# SCH_Andrew_s-NFC-Card_2024-04-20.net
KiCad netlist of a schematic drawn in EasyEDA
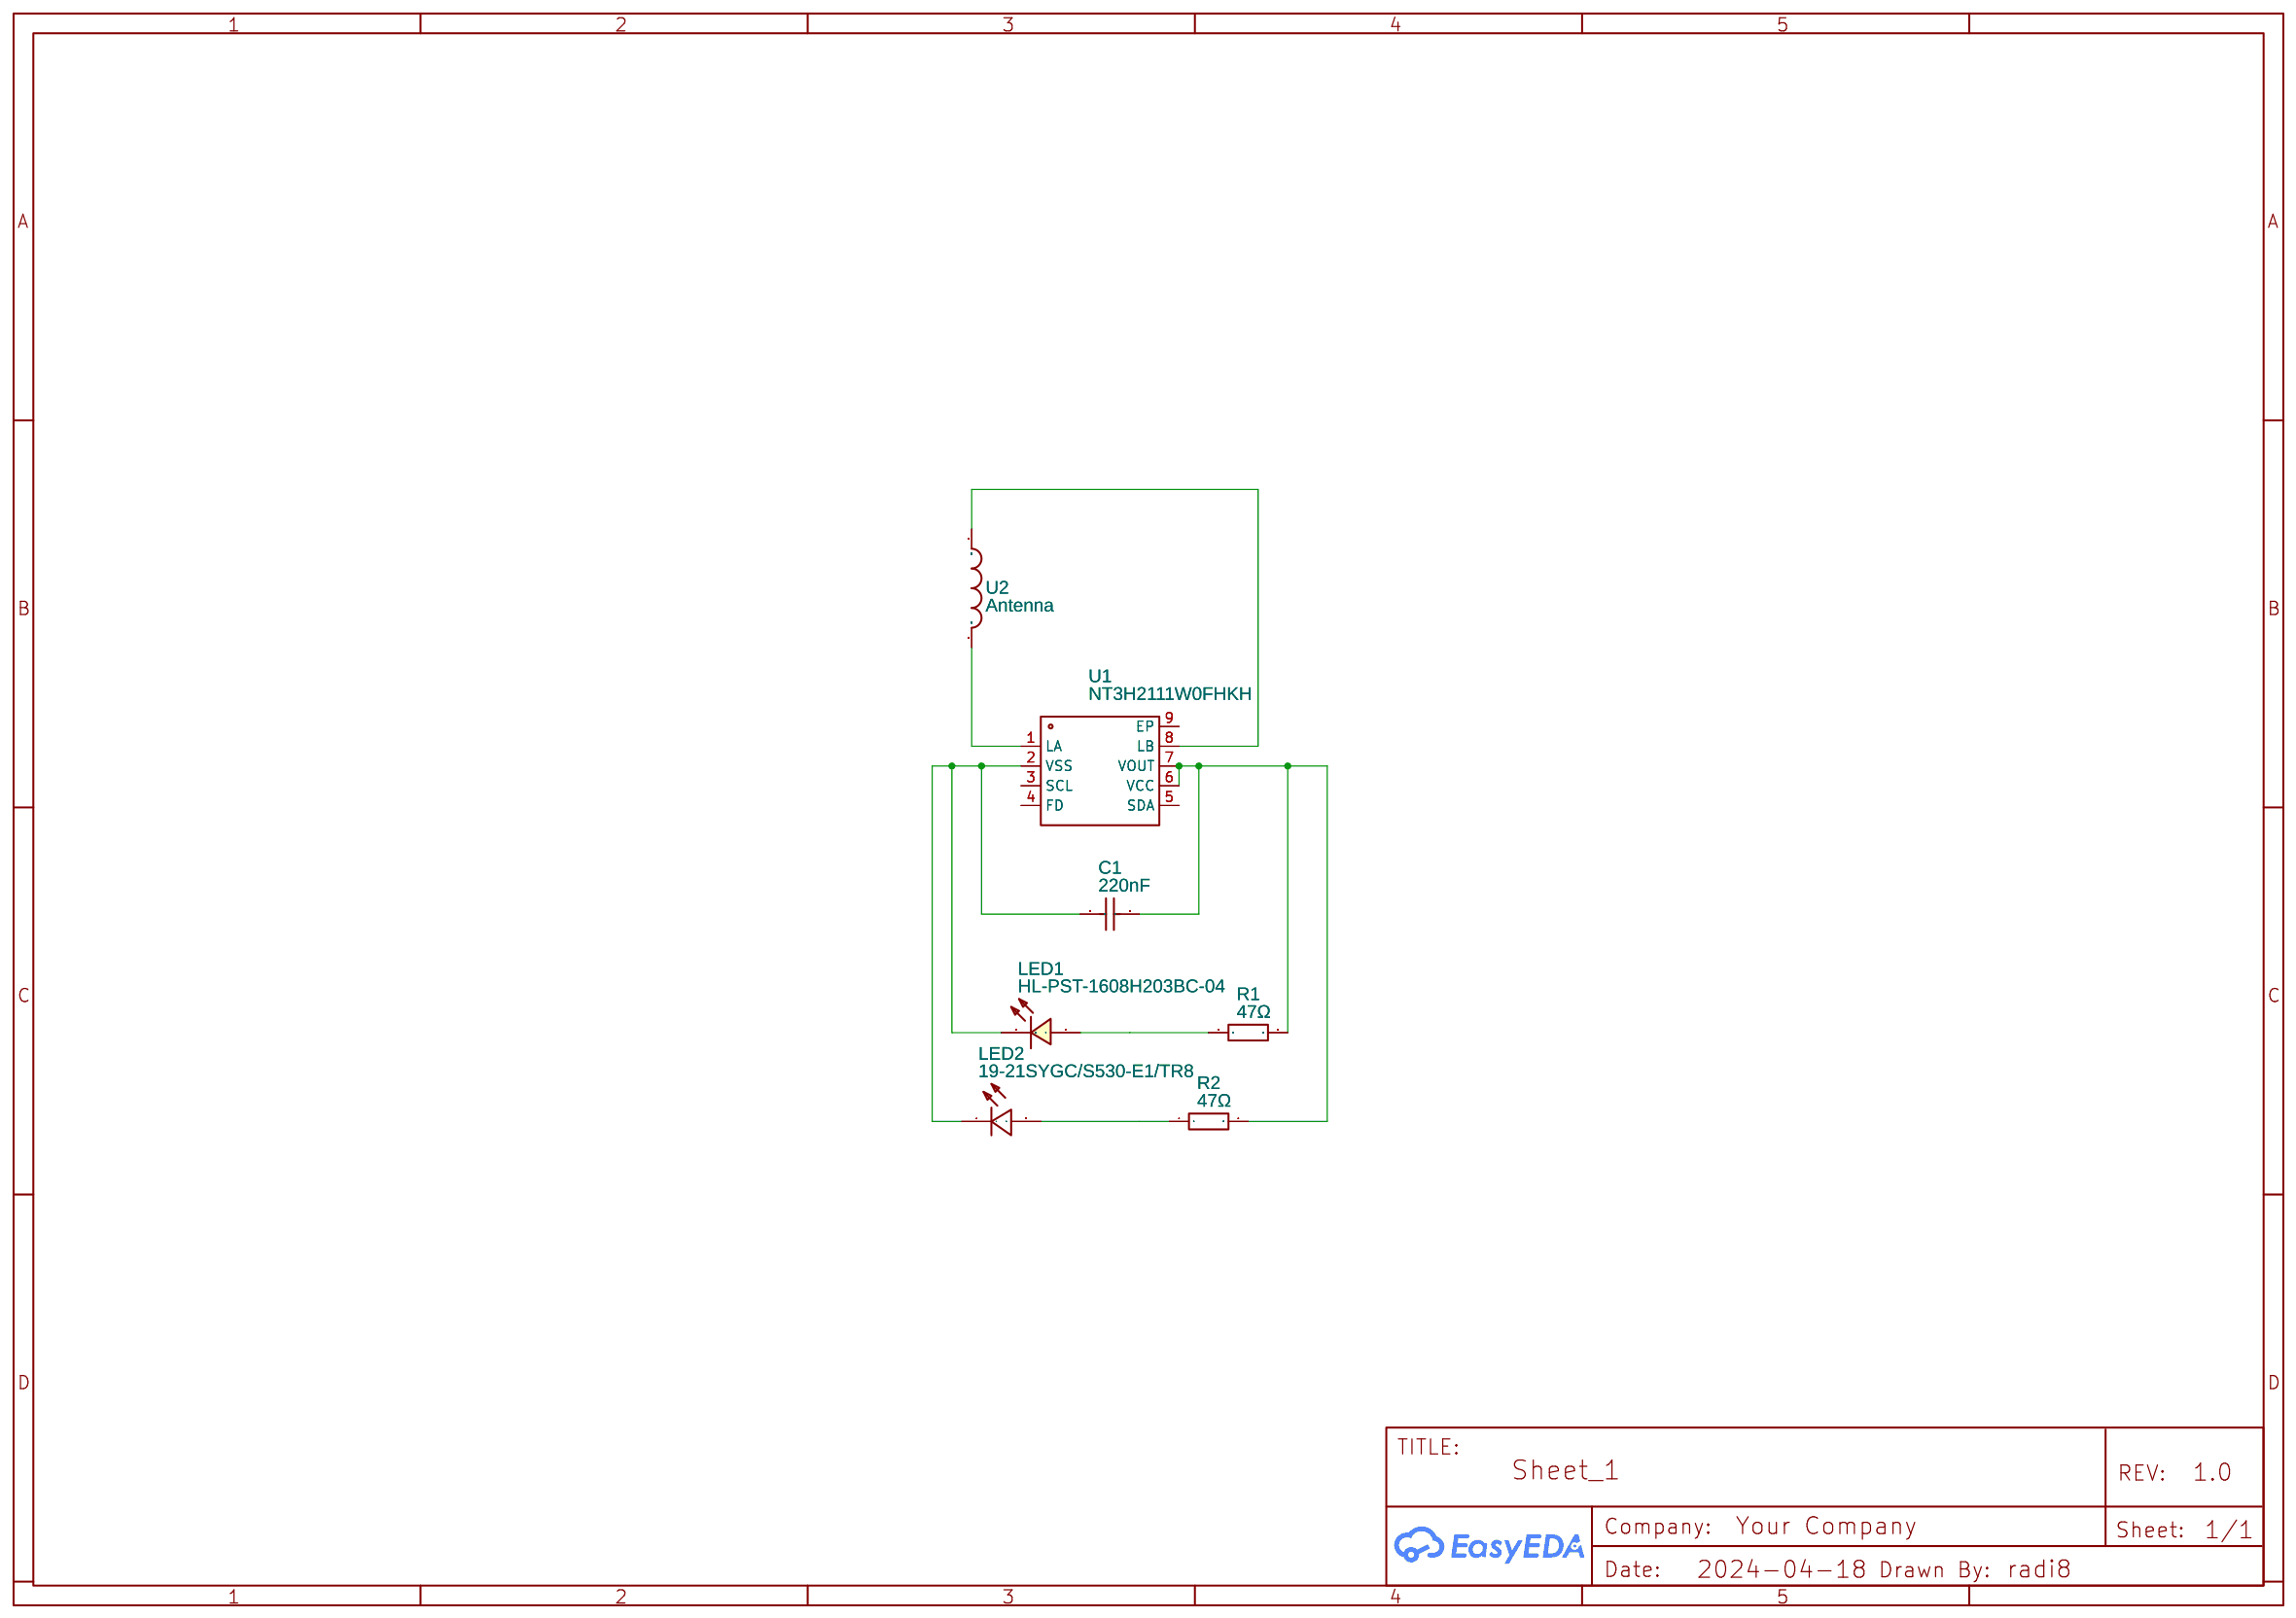
[diagram p0: schematic sheet]

(export (version "E")
  (design (tool "Eeschema 10.0.6"))
  (components
    (comp (ref "C1")
      (value "220nF")
      (fields
        (field (name "Manufacturer Part") "CL10B224KA8NNNC")
        (field (name "Manufacturer") "SAMSUNG(三星)")
      )
      (libsource (lib "") (part "CL10B224KA8NNNC"))
    )
    (comp (ref "LED1")
      (value "HL-PST-1608H203BC-04")
      (fields (field (name "Manufacturer") "HONGLITRONIC(鸿利光电)"))
      (libsource (lib "") (part "HL-PST-1608H203BC-04"))
    )
    (comp (ref "LED2") (value "19-21SYGC/S530-E1/TR8") (libsource (lib "") (part "19-21SYGC/S530-E1/TR8")))
    (comp (ref "R1")
      (value "47Ω")
      (fields
        (field (name "Manufacturer Part") "0603WAF470JT5E")
        (field (name "Manufacturer") "UNI-ROYAL(厚声)")
      )
      (libsource (lib "") (part "0603WAF470JT5E"))
    )
    (comp (ref "R2")
      (value "47Ω")
      (fields
        (field (name "Manufacturer Part") "0603WAF470JT5E")
        (field (name "Manufacturer") "UNI-ROYAL(厚声)")
      )
      (libsource (lib "") (part "0603WAF470JT5E"))
    )
    (comp (ref "U1")
      (value "NT3H2111W0FHKH")
      (fields (field (name "Manufacturer") "NXP(恩智浦)"))
      (libsource (lib "") (part "NT3H2111W0FHKH"))
    )
    (comp (ref "U2") (value "Antenna") (libsource (lib "") (part "Antenna")))
  )
  (nets
    (net (code "1") (name "Net-(LED1-A)") (class "Default")
      (node (ref "LED1") (pin "2") (pinfunction "A_2") (pintype "unspecified"))
      (node (ref "R1") (pin "1") (pinfunction "1_1") (pintype "input"))
    )
    (net (code "2") (name "Net-(LED1-C)") (class "Default")
      (node (ref "C1") (pin "1") (pinfunction "1_1") (pintype "input"))
      (node (ref "LED1") (pin "1") (pinfunction "C_1") (pintype "unspecified"))
      (node (ref "LED2") (pin "1") (pinfunction "-_1") (pintype "unspecified"))
      (node (ref "U1") (pin "2") (pinfunction "VSS_2") (pintype "unspecified"))
    )
    (net (code "3") (name "Net-(LED2-+)") (class "Default")
      (node (ref "LED2") (pin "2") (pinfunction "+_2") (pintype "unspecified"))
      (node (ref "R2") (pin "1") (pinfunction "1_1") (pintype "input"))
    )
    (net (code "4") (name "Net-(U1-LA)") (class "Default")
      (node (ref "U1") (pin "1") (pinfunction "LA_1") (pintype "unspecified"))
      (node (ref "U2") (pin "P$1") (pinfunction "P$1_P$1") (pintype "unspecified"))
    )
    (net (code "5") (name "Net-(U1-LB)") (class "Default")
      (node (ref "U1") (pin "8") (pinfunction "LB_8") (pintype "unspecified"))
      (node (ref "U2") (pin "P$2") (pinfunction "P$2_P$2") (pintype "unspecified"))
    )
    (net (code "6") (name "Net-(U1-VCC)") (class "Default")
      (node (ref "C1") (pin "2") (pinfunction "2_2") (pintype "input"))
      (node (ref "R1") (pin "2") (pinfunction "2_2") (pintype "input"))
      (node (ref "R2") (pin "2") (pinfunction "2_2") (pintype "input"))
      (node (ref "U1") (pin "6") (pinfunction "VCC_6") (pintype "unspecified"))
      (node (ref "U1") (pin "7") (pinfunction "VOUT_7") (pintype "unspecified"))
    )
    (net (code "7") (name "unconnected-(U1-EP-Pad9)") (class "Default")
      (node (ref "U1") (pin "9") (pinfunction "EP_9") (pintype "unspecified"))
    )
    (net (code "8") (name "unconnected-(U1-FD-Pad4)") (class "Default")
      (node (ref "U1") (pin "4") (pinfunction "FD_4") (pintype "unspecified"))
    )
    (net (code "9") (name "unconnected-(U1-SCL-Pad3)") (class "Default")
      (node (ref "U1") (pin "3") (pinfunction "SCL_3") (pintype "unspecified"))
    )
    (net (code "10") (name "unconnected-(U1-SDA-Pad5)") (class "Default")
      (node (ref "U1") (pin "5") (pinfunction "SDA_5") (pintype "unspecified"))
    )
  )
)
